# HAND_CAN_MCU.net
KiCad netlist of a schematic drawn in Altium Designer
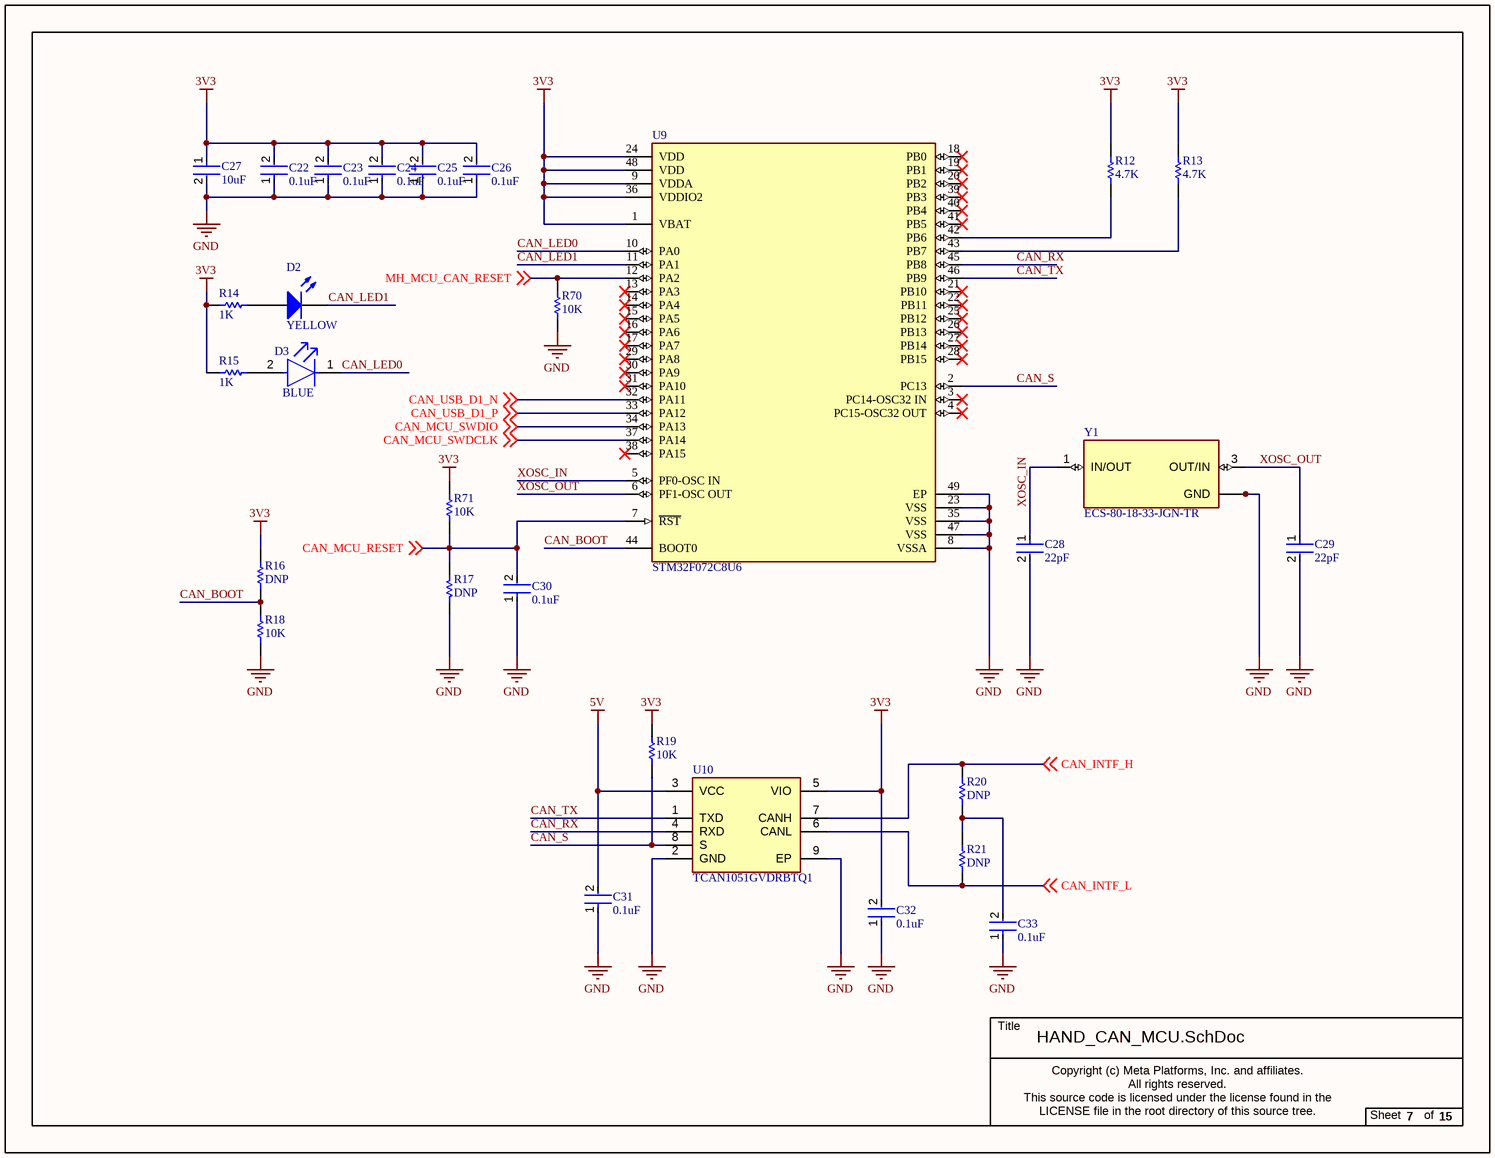
[diagram p0: HAND_CAN_MCU.SchDoc]

(export (version "E")
  (design (tool "Eeschema 10.0.6"))
  (components
    (comp (ref "C22")
      (value "0.1uF")
      (footprint "FP-CC0201-BA-MFG")
      (description "CAP CER 0.1UF 6.3V X5R 0201")
      (fields (field (name "MANUFACTURER") "Yageo") (field (name "TOLERANCE") "0.1"))
      (libsource (lib "Altium Content Vault") (part "11868f565c42a9108669ba33697ecf6"))
    )
    (comp (ref "C23")
      (value "0.1uF")
      (footprint "FP-CC0201-BA-MFG")
      (description "CAP CER 0.1UF 6.3V X5R 0201")
      (fields (field (name "MANUFACTURER") "Yageo") (field (name "TOLERANCE") "0.1"))
      (libsource (lib "Altium Content Vault") (part "11868f565c42a9108669ba33697ecf6"))
    )
    (comp (ref "C24")
      (value "0.1uF")
      (footprint "FP-CC0201-BA-MFG")
      (description "CAP CER 0.1UF 6.3V X5R 0201")
      (fields (field (name "MANUFACTURER") "Yageo") (field (name "TOLERANCE") "0.1"))
      (libsource (lib "Altium Content Vault") (part "11868f565c42a9108669ba33697ecf6"))
    )
    (comp (ref "C25")
      (value "0.1uF")
      (footprint "FP-CC0201-BA-MFG")
      (description "CAP CER 0.1UF 6.3V X5R 0201")
      (fields (field (name "MANUFACTURER") "Yageo") (field (name "TOLERANCE") "0.1"))
      (libsource (lib "Altium Content Vault") (part "11868f565c42a9108669ba33697ecf6"))
    )
    (comp (ref "C26")
      (value "0.1uF")
      (footprint "FP-CC0201-BA-MFG")
      (description "CAP CER 0.1UF 6.3V X5R 0201")
      (fields (field (name "MANUFACTURER") "Yageo") (field (name "TOLERANCE") "0.1"))
      (libsource (lib "Altium Content Vault") (part "11868f565c42a9108669ba33697ecf6"))
    )
    (comp (ref "C27")
      (value "10uF")
      (footprint "FP-CL05A106MP5NUNC-MFG")
      (description "CAP CER 10UF 10V X5R 0402")
      (fields
        (field (name "OCTOPART") "https://octopart.com/cl05a106mp5nunc-samsung-22457395")
        (field (name "TOLERANCE") "20%")
      )
      (libsource (lib "Altium Content Vault") (part "b4654b650e69147ec39a6b967a45e02"))
    )
    (comp (ref "C28")
      (value "22pF")
      (footprint "FP-0402-L_1_0_1-W_0_5_0_1-MFG")
      (description "General Purpose Ceramic Capacitor, 0402, 22pF, 5%, C0G, 30ppm/°C, 50V")
      (fields (field (name "VOLTAGE") "50V") (field (name "TOLERANCE") "5%"))
      (libsource (lib "Altium Content Vault") (part "b4654b650e69147ec39a6b967a45e02"))
    )
    (comp (ref "C29")
      (value "22pF")
      (footprint "FP-0402-L_1_0_1-W_0_5_0_1-MFG")
      (description "General Purpose Ceramic Capacitor, 0402, 22pF, 5%, C0G, 30ppm/°C, 50V")
      (fields (field (name "VOLTAGE") "50V") (field (name "TOLERANCE") "5%"))
      (libsource (lib "Altium Content Vault") (part "b4654b650e69147ec39a6b967a45e02"))
    )
    (comp (ref "C30")
      (value "0.1uF")
      (footprint "FP-CC0201-BA-MFG")
      (description "CAP CER 0.1UF 6.3V X5R 0201")
      (fields (field (name "MANUFACTURER") "Yageo") (field (name "TOLERANCE") "0.1"))
      (libsource (lib "Altium Content Vault") (part "11868f565c42a9108669ba33697ecf6"))
    )
    (comp (ref "C31")
      (value "0.1uF")
      (footprint "FP-CC0201-BA-MFG")
      (description "CAP CER 0.1UF 6.3V X5R 0201")
      (fields (field (name "MANUFACTURER") "Yageo") (field (name "TOLERANCE") "0.1"))
      (libsource (lib "Altium Content Vault") (part "11868f565c42a9108669ba33697ecf6"))
    )
    (comp (ref "C32")
      (value "0.1uF")
      (footprint "FP-CC0201-BA-MFG")
      (description "CAP CER 0.1UF 6.3V X5R 0201")
      (fields (field (name "MANUFACTURER") "Yageo") (field (name "TOLERANCE") "0.1"))
      (libsource (lib "Altium Content Vault") (part "11868f565c42a9108669ba33697ecf6"))
    )
    (comp (ref "C33")
      (value "0.1uF")
      (footprint "FP-CC0201-BA-MFG")
      (description "CAP CER 0.1UF 6.3V X5R 0201")
      (fields (field (name "MANUFACTURER") "Yageo") (field (name "TOLERANCE") "0.1"))
      (libsource (lib "Altium Content Vault") (part "11868f565c42a9108669ba33697ecf6"))
    )
    (comp (ref "D2")
      (value "YELLOW")
      (footprint "0603_A")
      (description "SMD mono-color Chip LED, WL-SMCW, Yellow")
      (fields (field (name "PARTNUMBER") "150060YS75000") (field (name "MANUFACTURER") "Wuerth Elektronik"))
      (libsource (lib "Altium Content Vault") (part "WE-LED_K1A2-2"))
    )
    (comp (ref "D3")
      (value "BLUE")
      (footprint "FP-LTST-C191TBKT-MFG")
      (description "LED BLUE CLEAR CHIP SMD")
      (libsource (lib "Altium Content Vault") (part "8706943c75ba83719d021d2fdc84c58"))
    )
    (comp (ref "R12")
      (value "4.7K")
      (footprint "RESC1005X40X25LL05T05")
      (description "Chip Resistor, 4.7 KOhm, +/- 1%, 0.1 W, -55 to 155 degC, 0402 (1005 Metric), RoHS, Tape and Reel")
      (fields (field (name "TOLERANCE") "1%") (field (name "PARTNUMBER") "ERJ-2RKF4701X"))
      (libsource (lib "Altium Content Vault") (part "RES-2"))
    )
    (comp (ref "R13")
      (value "4.7K")
      (footprint "RESC1005X40X25LL05T05")
      (description "Chip Resistor, 4.7 KOhm, +/- 1%, 0.1 W, -55 to 155 degC, 0402 (1005 Metric), RoHS, Tape and Reel")
      (fields (field (name "TOLERANCE") "1%") (field (name "PARTNUMBER") "ERJ-2RKF4701X"))
      (libsource (lib "Altium Content Vault") (part "RES-2"))
    )
    (comp (ref "R14")
      (value "1K")
      (footprint "RESC1005X40X25NL05T05")
      (description "Chip Resistor, 1 KOhm, +/- 1%, 100 mW, -55 to 155 degC, 0402 (1005 Metric), RoHS, Tape and Reel")
      (fields (field (name "PARTNUMBER") "ERJ-2RKF1001X") (field (name "MANUFACTURER") "Basic Passives"))
      (libsource (lib "Altium Content Vault") (part "RES-2"))
    )
    (comp (ref "R15")
      (value "1K")
      (footprint "RESC1005X40X25NL05T05")
      (description "Chip Resistor, 1 KOhm, +/- 1%, 100 mW, -55 to 155 degC, 0402 (1005 Metric), RoHS, Tape and Reel")
      (fields (field (name "PARTNUMBER") "ERJ-2RKF1001X") (field (name "MANUFACTURER") "Basic Passives"))
      (libsource (lib "Altium Content Vault") (part "RES-2"))
    )
    (comp (ref "R16")
      (value "DNP")
      (footprint "RESC1005X40X25ML05T10")
      (fields (field (name "PART NUMBER") "CRCW040210K0FKEDHP") (field (name "MANUFACTURER") "Vishay Dale"))
      (libsource (lib "Altium Content Vault") (part "RES"))
    )
    (comp (ref "R17")
      (value "DNP")
      (footprint "RESC1005X40X25NL05T10")
      (fields (field (name "MANUFACTURER") "Yageo / Phycomp") (field (name "PART NUMBER") "RC0402JR-070RL"))
      (libsource (lib "Altium Content Vault") (part "RES"))
    )
    (comp (ref "R18")
      (value "10K")
      (footprint "RESC1005X40X25ML05T10")
      (fields (field (name "PART NUMBER") "CRCW040210K0FKEDHP") (field (name "MANUFACTURER") "Vishay Dale"))
      (libsource (lib "Altium Content Vault") (part "RES"))
    )
    (comp (ref "R19")
      (value "10K")
      (footprint "RESC1005X40X25ML05T10")
      (fields (field (name "PART NUMBER") "CRCW040210K0FKEDHP") (field (name "MANUFACTURER") "Vishay Dale"))
      (libsource (lib "Altium Content Vault") (part "RES"))
    )
    (comp (ref "R20")
      (value "DNP")
      (footprint "RESC1005X40X25ML05T10")
      (fields (field (name "PART NUMBER") "CRCW040210K0FKEDHP") (field (name "MANUFACTURER") "Vishay Dale"))
      (libsource (lib "Altium Content Vault") (part "RES"))
    )
    (comp (ref "R21")
      (value "DNP")
      (footprint "RESC1005X40X25ML05T10")
      (fields (field (name "PART NUMBER") "CRCW040210K0FKEDHP") (field (name "MANUFACTURER") "Vishay Dale"))
      (libsource (lib "Altium Content Vault") (part "RES"))
    )
    (comp (ref "R70")
      (value "10K")
      (footprint "RESC1005X40X25ML05T10")
      (fields (field (name "PART NUMBER") "CRCW040210K0FKEDHP") (field (name "MANUFACTURER") "Vishay Dale"))
      (libsource (lib "Altium Content Vault") (part "RES"))
    )
    (comp (ref "R71")
      (value "10K")
      (footprint "RESC1005X40X25ML05T10")
      (fields (field (name "PART NUMBER") "CRCW040210K0FKEDHP") (field (name "MANUFACTURER") "Vishay Dale"))
      (libsource (lib "Altium Content Vault") (part "RES"))
    )
    (comp (ref "U9")
      (value "STM32F072C8U6")
      (footprint "FP-UFQFPN48-A0B9-MFG")
      (description "IC MCU 32BIT 64KB FLASH 48UFQFPN")
      (libsource (lib "Altium Content Vault") (part "f8255e7780ed971a7b08bf622c0a99f"))
    )
    (comp (ref "U10")
      (value "TCAN1051GVDRBTQ1")
      (footprint "SamacSys:SON65P300X300X100-9N-D")
      (description "Integrated Circuit")
      (fields (field (name "MOUSER PART NUMBER") "595-TCAN1051GVDRBTQ1"))
      (libsource (lib "*") (part "TCAN1051GVDRBTQ1"))
    )
    (comp (ref "Y1")
      (value "ECS-80-18-33-JGN-TR")
      (footprint "ECS-80-18-33-JGN-TR:XTAL_ECS-240-8-33-AGN-TR")
      (fields (field (name "MF") "{'manufacturer': u'ECS Inc.'}"))
      (libsource (lib "*") (part "ECS-80-18-33-JGN-TR"))
    )
  )
  (nets
    (net (code "1") (name "/CAN_BOOT") (class "Default")
      (node (ref "R16") (pin "1") (pinfunction "1_1") (pintype "passive"))
      (node (ref "R18") (pin "2") (pinfunction "2_2") (pintype "passive"))
      (node (ref "U9") (pin "44") (pinfunction "BOOT0_44") (pintype "passive"))
    )
    (net (code "2") (name "/CAN_LED0") (class "Default")
      (node (ref "D3") (pin "1") (pinfunction "C_1") (pintype "passive"))
      (node (ref "U9") (pin "10") (pinfunction "PA0_10") (pintype "bidirectional"))
    )
    (net (code "3") (name "/CAN_LED1") (class "Default")
      (node (ref "D2") (pin "1") (pinfunction "K_1") (pintype "passive"))
      (node (ref "U9") (pin "11") (pinfunction "PA1_11") (pintype "bidirectional"))
    )
    (net (code "4") (name "/CAN_RX") (class "Default")
      (node (ref "U10") (pin "4") (pinfunction "RXD_4") (pintype "passive"))
      (node (ref "U9") (pin "45") (pinfunction "PB8_45") (pintype "bidirectional"))
    )
    (net (code "5") (name "/CAN_S") (class "Default")
      (node (ref "R19") (pin "1") (pinfunction "1_1") (pintype "passive"))
      (node (ref "U10") (pin "8") (pinfunction "S_8") (pintype "passive"))
      (node (ref "U9") (pin "2") (pinfunction "PC13_2") (pintype "bidirectional"))
    )
    (net (code "6") (name "/CAN_TX") (class "Default")
      (node (ref "U10") (pin "1") (pinfunction "TXD_1") (pintype "passive"))
      (node (ref "U9") (pin "46") (pinfunction "PB9_46") (pintype "bidirectional"))
    )
    (net (code "7") (name "/XOSC_IN") (class "Default")
      (node (ref "C28") (pin "1") (pinfunction "1_1") (pintype "passive"))
      (node (ref "U9") (pin "5") (pinfunction "PF0-OSC_IN_5") (pintype "bidirectional"))
      (node (ref "Y1") (pin "1") (pinfunction "IN/OUT_1") (pintype "bidirectional"))
    )
    (net (code "8") (name "/XOSC_OUT") (class "Default")
      (node (ref "C29") (pin "1") (pinfunction "1_1") (pintype "passive"))
      (node (ref "U9") (pin "6") (pinfunction "PF1-OSC_OUT_6") (pintype "bidirectional"))
      (node (ref "Y1") (pin "3") (pinfunction "OUT/IN_3") (pintype "bidirectional"))
    )
    (net (code "9") (name "3V3") (class "Default")
      (node (ref "C22") (pin "2") (pinfunction "2_2") (pintype "passive"))
      (node (ref "C23") (pin "2") (pinfunction "2_2") (pintype "passive"))
      (node (ref "C24") (pin "2") (pinfunction "2_2") (pintype "passive"))
      (node (ref "C25") (pin "2") (pinfunction "2_2") (pintype "passive"))
      (node (ref "C26") (pin "2") (pinfunction "2_2") (pintype "passive"))
      (node (ref "C27") (pin "1") (pinfunction "1_1") (pintype "passive"))
      (node (ref "C32") (pin "2") (pinfunction "2_2") (pintype "passive"))
      (node (ref "R12") (pin "2") (pinfunction "2_2") (pintype "passive"))
      (node (ref "R13") (pin "2") (pinfunction "2_2") (pintype "passive"))
      (node (ref "R14") (pin "1") (pinfunction "1_1") (pintype "passive"))
      (node (ref "R15") (pin "1") (pinfunction "1_1") (pintype "passive"))
      (node (ref "R16") (pin "2") (pinfunction "2_2") (pintype "passive"))
      (node (ref "R19") (pin "2") (pinfunction "2_2") (pintype "passive"))
      (node (ref "R71") (pin "2") (pinfunction "2_2") (pintype "passive"))
      (node (ref "U10") (pin "5") (pinfunction "VIO_5") (pintype "passive"))
      (node (ref "U9") (pin "1") (pinfunction "VBAT_1") (pintype "power_in"))
      (node (ref "U9") (pin "24") (pinfunction "VDD_24") (pintype "power_in"))
      (node (ref "U9") (pin "36") (pinfunction "VDDIO2_36") (pintype "power_in"))
      (node (ref "U9") (pin "48") (pinfunction "VDD_48") (pintype "power_in"))
      (node (ref "U9") (pin "9") (pinfunction "VDDA_9") (pintype "power_in"))
    )
    (net (code "10") (name "5V") (class "Default")
      (node (ref "C31") (pin "2") (pinfunction "2_2") (pintype "passive"))
      (node (ref "U10") (pin "3") (pinfunction "VCC_3") (pintype "passive"))
    )
    (net (code "11") (name "CAN_INTF_H") (class "Default")
      (node (ref "R20") (pin "2") (pinfunction "2_2") (pintype "passive"))
      (node (ref "U10") (pin "7") (pinfunction "CANH_7") (pintype "passive"))
    )
    (net (code "12") (name "CAN_INTF_L") (class "Default")
      (node (ref "R21") (pin "1") (pinfunction "1_1") (pintype "passive"))
      (node (ref "U10") (pin "6") (pinfunction "CANL_6") (pintype "passive"))
    )
    (net (code "13") (name "CAN_MCU_RESET") (class "Default")
      (node (ref "C30") (pin "2") (pinfunction "2_2") (pintype "passive"))
      (node (ref "R17") (pin "2") (pinfunction "2_2") (pintype "passive"))
      (node (ref "R71") (pin "1") (pinfunction "1_1") (pintype "passive"))
      (node (ref "U9") (pin "7") (pinfunction "~{RST}_7") (pintype "input"))
    )
    (net (code "14") (name "CAN_MCU_SWDCLK") (class "Default")
      (node (ref "U9") (pin "37") (pinfunction "PA14_37") (pintype "bidirectional"))
    )
    (net (code "15") (name "CAN_MCU_SWDIO") (class "Default")
      (node (ref "U9") (pin "34") (pinfunction "PA13_34") (pintype "bidirectional"))
    )
    (net (code "16") (name "CAN_USB_D1_N") (class "Default")
      (node (ref "U9") (pin "32") (pinfunction "PA11_32") (pintype "bidirectional"))
    )
    (net (code "17") (name "CAN_USB_D1_P") (class "Default")
      (node (ref "U9") (pin "33") (pinfunction "PA12_33") (pintype "bidirectional"))
    )
    (net (code "18") (name "GND") (class "Default")
      (node (ref "C22") (pin "1") (pinfunction "1_1") (pintype "passive"))
      (node (ref "C23") (pin "1") (pinfunction "1_1") (pintype "passive"))
      (node (ref "C24") (pin "1") (pinfunction "1_1") (pintype "passive"))
      (node (ref "C25") (pin "1") (pinfunction "1_1") (pintype "passive"))
      (node (ref "C26") (pin "1") (pinfunction "1_1") (pintype "passive"))
      (node (ref "C27") (pin "2") (pinfunction "2_2") (pintype "passive"))
      (node (ref "C28") (pin "2") (pinfunction "2_2") (pintype "passive"))
      (node (ref "C29") (pin "2") (pinfunction "2_2") (pintype "passive"))
      (node (ref "C30") (pin "1") (pinfunction "1_1") (pintype "passive"))
      (node (ref "C31") (pin "1") (pinfunction "1_1") (pintype "passive"))
      (node (ref "C32") (pin "1") (pinfunction "1_1") (pintype "passive"))
      (node (ref "C33") (pin "1") (pinfunction "1_1") (pintype "passive"))
      (node (ref "R17") (pin "1") (pinfunction "1_1") (pintype "passive"))
      (node (ref "R18") (pin "1") (pinfunction "1_1") (pintype "passive"))
      (node (ref "R70") (pin "1") (pinfunction "1_1") (pintype "passive"))
      (node (ref "U10") (pin "2") (pinfunction "GND_2") (pintype "passive"))
      (node (ref "U10") (pin "9") (pinfunction "EP_9") (pintype "passive"))
      (node (ref "U9") (pin "23") (pinfunction "VSS_23") (pintype "power_in"))
      (node (ref "U9") (pin "35") (pinfunction "VSS_35") (pintype "power_in"))
      (node (ref "U9") (pin "47") (pinfunction "VSS_47") (pintype "power_in"))
      (node (ref "U9") (pin "49") (pinfunction "EP_49") (pintype "power_in"))
      (node (ref "U9") (pin "8") (pinfunction "VSSA_8") (pintype "power_in"))
      (node (ref "Y1") (pin "2") (pinfunction "GND_2") (pintype "power_in"))
      (node (ref "Y1") (pin "4") (pinfunction "GND_4") (pintype "power_in"))
    )
    (net (code "19") (name "MH_MCU_CAN_RESET") (class "Default")
      (node (ref "R70") (pin "2") (pinfunction "2_2") (pintype "passive"))
      (node (ref "U9") (pin "12") (pinfunction "PA2_12") (pintype "bidirectional"))
    )
    (net (code "20") (name "Net-(C33-Pad2)") (class "Default")
      (node (ref "C33") (pin "2") (pinfunction "2_2") (pintype "passive"))
      (node (ref "R20") (pin "1") (pinfunction "1_1") (pintype "passive"))
      (node (ref "R21") (pin "2") (pinfunction "2_2") (pintype "passive"))
    )
    (net (code "21") (name "Net-(D2-A)") (class "Default")
      (node (ref "D2") (pin "2") (pinfunction "A_2") (pintype "passive"))
      (node (ref "R14") (pin "2") (pinfunction "2_2") (pintype "passive"))
    )
    (net (code "22") (name "Net-(D3-A)") (class "Default")
      (node (ref "D3") (pin "2") (pinfunction "A_2") (pintype "passive"))
      (node (ref "R15") (pin "2") (pinfunction "2_2") (pintype "passive"))
    )
    (net (code "23") (name "Net-(U9-PB6)") (class "Default")
      (node (ref "R12") (pin "1") (pinfunction "1_1") (pintype "passive"))
      (node (ref "U9") (pin "42") (pinfunction "PB6_42") (pintype "bidirectional"))
    )
    (net (code "24") (name "Net-(U9-PB7)") (class "Default")
      (node (ref "R13") (pin "1") (pinfunction "1_1") (pintype "passive"))
      (node (ref "U9") (pin "43") (pinfunction "PB7_43") (pintype "bidirectional"))
    )
    (net (code "25") (name "unconnected-(U9-PA3-Pad13)") (class "Default")
      (node (ref "U9") (pin "13") (pinfunction "PA3_13") (pintype "bidirectional+no_connect"))
    )
    (net (code "26") (name "unconnected-(U9-PA4-Pad14)") (class "Default")
      (node (ref "U9") (pin "14") (pinfunction "PA4_14") (pintype "bidirectional+no_connect"))
    )
    (net (code "27") (name "unconnected-(U9-PA5-Pad15)") (class "Default")
      (node (ref "U9") (pin "15") (pinfunction "PA5_15") (pintype "bidirectional+no_connect"))
    )
    (net (code "28") (name "unconnected-(U9-PA6-Pad16)") (class "Default")
      (node (ref "U9") (pin "16") (pinfunction "PA6_16") (pintype "bidirectional+no_connect"))
    )
    (net (code "29") (name "unconnected-(U9-PA7-Pad17)") (class "Default")
      (node (ref "U9") (pin "17") (pinfunction "PA7_17") (pintype "bidirectional+no_connect"))
    )
    (net (code "30") (name "unconnected-(U9-PA8-Pad29)") (class "Default")
      (node (ref "U9") (pin "29") (pinfunction "PA8_29") (pintype "bidirectional+no_connect"))
    )
    (net (code "31") (name "unconnected-(U9-PA9-Pad30)") (class "Default")
      (node (ref "U9") (pin "30") (pinfunction "PA9_30") (pintype "bidirectional+no_connect"))
    )
    (net (code "32") (name "unconnected-(U9-PA10-Pad31)") (class "Default")
      (node (ref "U9") (pin "31") (pinfunction "PA10_31") (pintype "bidirectional+no_connect"))
    )
    (net (code "33") (name "unconnected-(U9-PA15-Pad38)") (class "Default")
      (node (ref "U9") (pin "38") (pinfunction "PA15_38") (pintype "bidirectional+no_connect"))
    )
    (net (code "34") (name "unconnected-(U9-PB0-Pad18)") (class "Default")
      (node (ref "U9") (pin "18") (pinfunction "PB0_18") (pintype "bidirectional+no_connect"))
    )
    (net (code "35") (name "unconnected-(U9-PB1-Pad19)") (class "Default")
      (node (ref "U9") (pin "19") (pinfunction "PB1_19") (pintype "bidirectional+no_connect"))
    )
    (net (code "36") (name "unconnected-(U9-PB2-Pad20)") (class "Default")
      (node (ref "U9") (pin "20") (pinfunction "PB2_20") (pintype "bidirectional+no_connect"))
    )
    (net (code "37") (name "unconnected-(U9-PB3-Pad39)") (class "Default")
      (node (ref "U9") (pin "39") (pinfunction "PB3_39") (pintype "bidirectional+no_connect"))
    )
    (net (code "38") (name "unconnected-(U9-PB4-Pad40)") (class "Default")
      (node (ref "U9") (pin "40") (pinfunction "PB4_40") (pintype "bidirectional+no_connect"))
    )
    (net (code "39") (name "unconnected-(U9-PB5-Pad41)") (class "Default")
      (node (ref "U9") (pin "41") (pinfunction "PB5_41") (pintype "bidirectional+no_connect"))
    )
    (net (code "40") (name "unconnected-(U9-PB10-Pad21)") (class "Default")
      (node (ref "U9") (pin "21") (pinfunction "PB10_21") (pintype "bidirectional+no_connect"))
    )
    (net (code "41") (name "unconnected-(U9-PB11-Pad22)") (class "Default")
      (node (ref "U9") (pin "22") (pinfunction "PB11_22") (pintype "bidirectional+no_connect"))
    )
    (net (code "42") (name "unconnected-(U9-PB12-Pad25)") (class "Default")
      (node (ref "U9") (pin "25") (pinfunction "PB12_25") (pintype "bidirectional+no_connect"))
    )
    (net (code "43") (name "unconnected-(U9-PB13-Pad26)") (class "Default")
      (node (ref "U9") (pin "26") (pinfunction "PB13_26") (pintype "bidirectional+no_connect"))
    )
    (net (code "44") (name "unconnected-(U9-PB14-Pad27)") (class "Default")
      (node (ref "U9") (pin "27") (pinfunction "PB14_27") (pintype "bidirectional+no_connect"))
    )
    (net (code "45") (name "unconnected-(U9-PB15-Pad28)") (class "Default")
      (node (ref "U9") (pin "28") (pinfunction "PB15_28") (pintype "bidirectional+no_connect"))
    )
    (net (code "46") (name "unconnected-(U9-PC14-OSC32_IN-Pad3)") (class "Default")
      (node (ref "U9") (pin "3") (pinfunction "PC14-OSC32_IN_3") (pintype "bidirectional+no_connect"))
    )
    (net (code "47") (name "unconnected-(U9-PC15-OSC32_OUT-Pad4)") (class "Default")
      (node (ref "U9") (pin "4") (pinfunction "PC15-OSC32_OUT_4") (pintype "bidirectional+no_connect"))
    )
  )
)
